# HVAC8-3.net
KiCad netlist of a schematic drawn in EAGLE
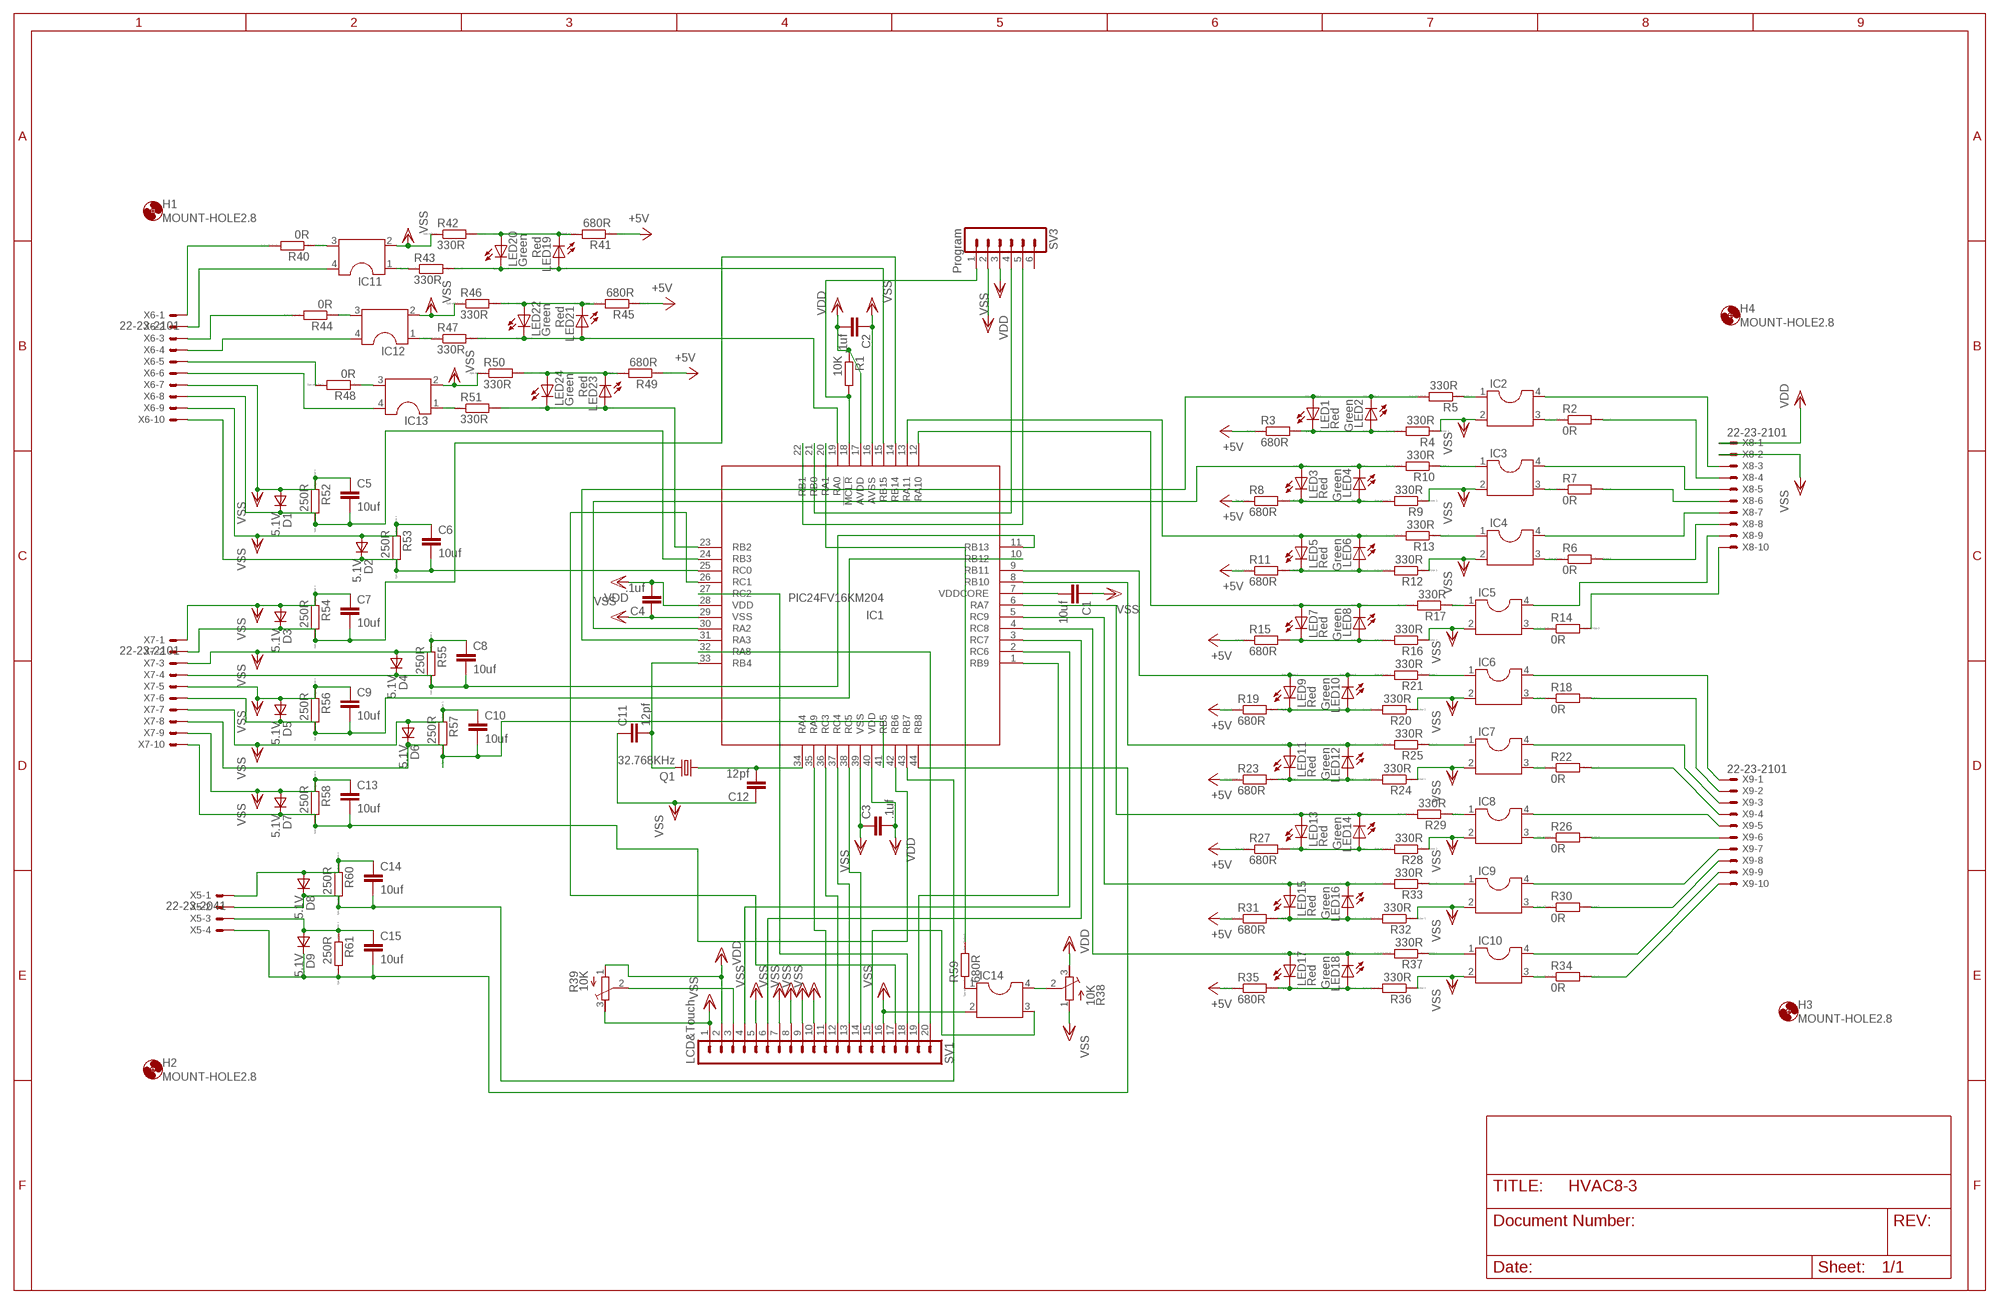
[diagram p0: schematic, sheet 1]

(export (version "E")
  (design (tool "Eeschema 10.0.6"))
  (components
    (comp (ref "C1")
      (value "10uf")
      (footprint "eagle-import:C1206")
      (libsource (lib "eagle-import") (part "C-EUC1206"))
    )
    (comp (ref "C2")
      (value ".1uf")
      (footprint "eagle-import:C1206")
      (libsource (lib "eagle-import") (part "C-EUC1206"))
    )
    (comp (ref "C3")
      (value ".1uf")
      (footprint "eagle-import:C1206")
      (libsource (lib "eagle-import") (part "C-EUC1206"))
    )
    (comp (ref "C4")
      (value ".1uf")
      (footprint "eagle-import:C1206")
      (libsource (lib "eagle-import") (part "C-EUC1206"))
    )
    (comp (ref "C5")
      (value "10uf")
      (footprint "eagle-import:C1206")
      (libsource (lib "eagle-import") (part "C-EUC1206"))
    )
    (comp (ref "C6")
      (value "10uf")
      (footprint "eagle-import:C1206")
      (libsource (lib "eagle-import") (part "C-EUC1206"))
    )
    (comp (ref "C7")
      (value "10uf")
      (footprint "eagle-import:C1206")
      (libsource (lib "eagle-import") (part "C-EUC1206"))
    )
    (comp (ref "C8")
      (value "10uf")
      (footprint "eagle-import:C1206")
      (libsource (lib "eagle-import") (part "C-EUC1206"))
    )
    (comp (ref "C9")
      (value "10uf")
      (footprint "eagle-import:C1206")
      (libsource (lib "eagle-import") (part "C-EUC1206"))
    )
    (comp (ref "C10")
      (value "10uf")
      (footprint "eagle-import:C1206")
      (libsource (lib "eagle-import") (part "C-EUC1206"))
    )
    (comp (ref "C11")
      (value "12pf")
      (footprint "eagle-import:C0603")
      (libsource (lib "eagle-import") (part "C-EUC0603"))
    )
    (comp (ref "C12")
      (value "12pf")
      (footprint "eagle-import:C0603")
      (libsource (lib "eagle-import") (part "C-EUC0603"))
    )
    (comp (ref "C13")
      (value "10uf")
      (footprint "eagle-import:C1206")
      (libsource (lib "eagle-import") (part "C-EUC1206"))
    )
    (comp (ref "C14")
      (value "10uf")
      (footprint "eagle-import:C1206")
      (libsource (lib "eagle-import") (part "C-EUC1206"))
    )
    (comp (ref "C15")
      (value "10uf")
      (footprint "eagle-import:C1206")
      (libsource (lib "eagle-import") (part "C-EUC1206"))
    )
    (comp (ref "D1")
      (value "5.1V")
      (footprint "eagle-import:SOD323")
      (fields (field (name "MPN") "CDSOD323-T05C"))
      (libsource (lib "eagle-import") (part "DSOD323"))
    )
    (comp (ref "D2")
      (value "5.1V")
      (footprint "eagle-import:SOD323")
      (fields (field (name "MPN") "CDSOD323-T05C"))
      (libsource (lib "eagle-import") (part "DSOD323"))
    )
    (comp (ref "D3")
      (value "5.1V")
      (footprint "eagle-import:SOD323")
      (fields (field (name "MPN") "CDSOD323-T05C"))
      (libsource (lib "eagle-import") (part "DSOD323"))
    )
    (comp (ref "D4")
      (value "5.1V")
      (footprint "eagle-import:SOD323")
      (fields (field (name "MPN") "CDSOD323-T05C"))
      (libsource (lib "eagle-import") (part "DSOD323"))
    )
    (comp (ref "D5")
      (value "5.1V")
      (footprint "eagle-import:SOD323")
      (fields (field (name "MPN") "CDSOD323-T05C"))
      (libsource (lib "eagle-import") (part "DSOD323"))
    )
    (comp (ref "D6")
      (value "5.1V")
      (footprint "eagle-import:SOD323")
      (fields (field (name "MPN") "CDSOD323-T05C"))
      (libsource (lib "eagle-import") (part "DSOD323"))
    )
    (comp (ref "D7")
      (value "5.1V")
      (footprint "eagle-import:SOD323")
      (fields (field (name "MPN") "CDSOD323-T05C"))
      (libsource (lib "eagle-import") (part "DSOD323"))
    )
    (comp (ref "D8")
      (value "5.1V")
      (footprint "eagle-import:SOD323")
      (fields (field (name "MPN") "CDSOD323-T05C"))
      (libsource (lib "eagle-import") (part "DSOD323"))
    )
    (comp (ref "D9")
      (value "5.1V")
      (footprint "eagle-import:SOD323")
      (fields (field (name "MPN") "CDSOD323-T05C"))
      (libsource (lib "eagle-import") (part "DSOD323"))
    )
    (comp (ref "H1")
      (value "MOUNT-HOLE2.8")
      (footprint "eagle-import:2,8")
      (libsource (lib "eagle-import") (part "MOUNT-HOLE2.8"))
    )
    (comp (ref "H2")
      (value "MOUNT-HOLE2.8")
      (footprint "eagle-import:2,8")
      (libsource (lib "eagle-import") (part "MOUNT-HOLE2.8"))
    )
    (comp (ref "H3")
      (value "MOUNT-HOLE2.8")
      (footprint "eagle-import:2,8")
      (libsource (lib "eagle-import") (part "MOUNT-HOLE2.8"))
    )
    (comp (ref "H4")
      (value "MOUNT-HOLE2.8")
      (footprint "eagle-import:2,8")
      (libsource (lib "eagle-import") (part "MOUNT-HOLE2.8"))
    )
    (comp (ref "IC1")
      (value "PIC24FV16KM204")
      (footprint "eagle-import:TQFP44")
      (libsource (lib "eagle-import") (part "PIC24FV16KM204"))
    )
    (comp (ref "IC2")
      (value "DIL4S")
      (footprint "eagle-import:SOCKET-04")
      (libsource (lib "eagle-import") (part "DIL4S"))
    )
    (comp (ref "IC3")
      (value "DIL4S")
      (footprint "eagle-import:SOCKET-04")
      (libsource (lib "eagle-import") (part "DIL4S"))
    )
    (comp (ref "IC4")
      (value "DIL4S")
      (footprint "eagle-import:SOCKET-04")
      (libsource (lib "eagle-import") (part "DIL4S"))
    )
    (comp (ref "IC5")
      (value "DIL4S")
      (footprint "eagle-import:SOCKET-04")
      (libsource (lib "eagle-import") (part "DIL4S"))
    )
    (comp (ref "IC6")
      (value "DIL4S")
      (footprint "eagle-import:SOCKET-04")
      (libsource (lib "eagle-import") (part "DIL4S"))
    )
    (comp (ref "IC7")
      (value "DIL4S")
      (footprint "eagle-import:SOCKET-04")
      (libsource (lib "eagle-import") (part "DIL4S"))
    )
    (comp (ref "IC8")
      (value "DIL4S")
      (footprint "eagle-import:SOCKET-04")
      (libsource (lib "eagle-import") (part "DIL4S"))
    )
    (comp (ref "IC9")
      (value "DIL4S")
      (footprint "eagle-import:SOCKET-04")
      (libsource (lib "eagle-import") (part "DIL4S"))
    )
    (comp (ref "IC10")
      (value "DIL4S")
      (footprint "eagle-import:SOCKET-04")
      (libsource (lib "eagle-import") (part "DIL4S"))
    )
    (comp (ref "IC11")
      (value "DIL4S")
      (footprint "eagle-import:SOCKET-04")
      (libsource (lib "eagle-import") (part "DIL4S"))
    )
    (comp (ref "IC12")
      (value "DIL4S")
      (footprint "eagle-import:SOCKET-04")
      (libsource (lib "eagle-import") (part "DIL4S"))
    )
    (comp (ref "IC13")
      (value "DIL4S")
      (footprint "eagle-import:SOCKET-04")
      (libsource (lib "eagle-import") (part "DIL4S"))
    )
    (comp (ref "IC14")
      (value "DIL4S")
      (footprint "eagle-import:SOCKET-04")
      (libsource (lib "eagle-import") (part "DIL4S"))
    )
    (comp (ref "LED1")
      (value "Red")
      (footprint "eagle-import:LED_1206")
      (libsource (lib "eagle-import") (part "LED_E"))
    )
    (comp (ref "LED2")
      (value "Green")
      (footprint "eagle-import:LED_1206")
      (libsource (lib "eagle-import") (part "LED_E"))
    )
    (comp (ref "LED3")
      (value "Red")
      (footprint "eagle-import:LED_1206")
      (libsource (lib "eagle-import") (part "LED_E"))
    )
    (comp (ref "LED4")
      (value "Green")
      (footprint "eagle-import:LED_1206")
      (libsource (lib "eagle-import") (part "LED_E"))
    )
    (comp (ref "LED5")
      (value "Red")
      (footprint "eagle-import:LED_1206")
      (libsource (lib "eagle-import") (part "LED_E"))
    )
    (comp (ref "LED6")
      (value "Green")
      (footprint "eagle-import:LED_1206")
      (libsource (lib "eagle-import") (part "LED_E"))
    )
    (comp (ref "LED7")
      (value "Red")
      (footprint "eagle-import:LED_1206")
      (libsource (lib "eagle-import") (part "LED_E"))
    )
    (comp (ref "LED8")
      (value "Green")
      (footprint "eagle-import:LED_1206")
      (libsource (lib "eagle-import") (part "LED_E"))
    )
    (comp (ref "LED9")
      (value "Red")
      (footprint "eagle-import:LED_1206")
      (libsource (lib "eagle-import") (part "LED_E"))
    )
    (comp (ref "LED10")
      (value "Green")
      (footprint "eagle-import:LED_1206")
      (libsource (lib "eagle-import") (part "LED_E"))
    )
    (comp (ref "LED11")
      (value "Red")
      (footprint "eagle-import:LED_1206")
      (libsource (lib "eagle-import") (part "LED_E"))
    )
    (comp (ref "LED12")
      (value "Green")
      (footprint "eagle-import:LED_1206")
      (libsource (lib "eagle-import") (part "LED_E"))
    )
    (comp (ref "LED13")
      (value "Red")
      (footprint "eagle-import:LED_1206")
      (libsource (lib "eagle-import") (part "LED_E"))
    )
    (comp (ref "LED14")
      (value "Green")
      (footprint "eagle-import:LED_1206")
      (libsource (lib "eagle-import") (part "LED_E"))
    )
    (comp (ref "LED15")
      (value "Red")
      (footprint "eagle-import:LED_1206")
      (libsource (lib "eagle-import") (part "LED_E"))
    )
    (comp (ref "LED16")
      (value "Green")
      (footprint "eagle-import:LED_1206")
      (libsource (lib "eagle-import") (part "LED_E"))
    )
    (comp (ref "LED17")
      (value "Red")
      (footprint "eagle-import:LED_1206")
      (libsource (lib "eagle-import") (part "LED_E"))
    )
    (comp (ref "LED18")
      (value "Green")
      (footprint "eagle-import:LED_1206")
      (libsource (lib "eagle-import") (part "LED_E"))
    )
    (comp (ref "LED19")
      (value "Red")
      (footprint "eagle-import:LED_1206")
      (libsource (lib "eagle-import") (part "LED_E"))
    )
    (comp (ref "LED20")
      (value "Green")
      (footprint "eagle-import:LED_1206")
      (libsource (lib "eagle-import") (part "LED_E"))
    )
    (comp (ref "LED21")
      (value "Red")
      (footprint "eagle-import:LED_1206")
      (libsource (lib "eagle-import") (part "LED_E"))
    )
    (comp (ref "LED22")
      (value "Green")
      (footprint "eagle-import:LED_1206")
      (libsource (lib "eagle-import") (part "LED_E"))
    )
    (comp (ref "LED23")
      (value "Red")
      (footprint "eagle-import:LED_1206")
      (libsource (lib "eagle-import") (part "LED_E"))
    )
    (comp (ref "LED24")
      (value "Green")
      (footprint "eagle-import:LED_1206")
      (libsource (lib "eagle-import") (part "LED_E"))
    )
    (comp (ref "Q1")
      (value "32.768KHz")
      (footprint "eagle-import:TC26H")
      (libsource (lib "eagle-import") (part "CRYSTALTC26H"))
    )
    (comp (ref "R1")
      (value "10K")
      (footprint "eagle-import:R1206")
      (libsource (lib "eagle-import") (part "R-EU_R1206"))
    )
    (comp (ref "R2")
      (value "0R")
      (footprint "eagle-import:R1206")
      (libsource (lib "eagle-import") (part "RR1206"))
    )
    (comp (ref "R3")
      (value "680R")
      (footprint "eagle-import:R1206")
      (libsource (lib "eagle-import") (part "RR1206"))
    )
    (comp (ref "R4")
      (value "330R")
      (footprint "eagle-import:R1206")
      (libsource (lib "eagle-import") (part "RR1206"))
    )
    (comp (ref "R5")
      (value "330R")
      (footprint "eagle-import:R1206")
      (libsource (lib "eagle-import") (part "RR1206"))
    )
    (comp (ref "R6")
      (value "0R")
      (footprint "eagle-import:R1206")
      (libsource (lib "eagle-import") (part "RR1206"))
    )
    (comp (ref "R7")
      (value "0R")
      (footprint "eagle-import:R1206")
      (libsource (lib "eagle-import") (part "RR1206"))
    )
    (comp (ref "R8")
      (value "680R")
      (footprint "eagle-import:R1206")
      (libsource (lib "eagle-import") (part "RR1206"))
    )
    (comp (ref "R9")
      (value "330R")
      (footprint "eagle-import:R1206")
      (libsource (lib "eagle-import") (part "RR1206"))
    )
    (comp (ref "R10")
      (value "330R")
      (footprint "eagle-import:R1206")
      (libsource (lib "eagle-import") (part "RR1206"))
    )
    (comp (ref "R11")
      (value "680R")
      (footprint "eagle-import:R1206")
      (libsource (lib "eagle-import") (part "RR1206"))
    )
    (comp (ref "R12")
      (value "330R")
      (footprint "eagle-import:R1206")
      (libsource (lib "eagle-import") (part "RR1206"))
    )
    (comp (ref "R13")
      (value "330R")
      (footprint "eagle-import:R1206")
      (libsource (lib "eagle-import") (part "RR1206"))
    )
    (comp (ref "R14")
      (value "0R")
      (footprint "eagle-import:R1206")
      (libsource (lib "eagle-import") (part "RR1206"))
    )
    (comp (ref "R15")
      (value "680R")
      (footprint "eagle-import:R1206")
      (libsource (lib "eagle-import") (part "RR1206"))
    )
    (comp (ref "R16")
      (value "330R")
      (footprint "eagle-import:R1206")
      (libsource (lib "eagle-import") (part "RR1206"))
    )
    (comp (ref "R17")
      (value "330R")
      (footprint "eagle-import:R1206")
      (libsource (lib "eagle-import") (part "RR1206"))
    )
    (comp (ref "R18")
      (value "0R")
      (footprint "eagle-import:R1206")
      (libsource (lib "eagle-import") (part "RR1206"))
    )
    (comp (ref "R19")
      (value "680R")
      (footprint "eagle-import:R1206")
      (libsource (lib "eagle-import") (part "RR1206"))
    )
    (comp (ref "R20")
      (value "330R")
      (footprint "eagle-import:R1206")
      (libsource (lib "eagle-import") (part "RR1206"))
    )
    (comp (ref "R21")
      (value "330R")
      (footprint "eagle-import:R1206")
      (libsource (lib "eagle-import") (part "RR1206"))
    )
    (comp (ref "R22")
      (value "0R")
      (footprint "eagle-import:R1206")
      (libsource (lib "eagle-import") (part "RR1206"))
    )
    (comp (ref "R23")
      (value "680R")
      (footprint "eagle-import:R1206")
      (libsource (lib "eagle-import") (part "RR1206"))
    )
    (comp (ref "R24")
      (value "330R")
      (footprint "eagle-import:R1206")
      (libsource (lib "eagle-import") (part "RR1206"))
    )
    (comp (ref "R25")
      (value "330R")
      (footprint "eagle-import:R1206")
      (libsource (lib "eagle-import") (part "RR1206"))
    )
    (comp (ref "R26")
      (value "0R")
      (footprint "eagle-import:R1206")
      (libsource (lib "eagle-import") (part "RR1206"))
    )
    (comp (ref "R27")
      (value "680R")
      (footprint "eagle-import:R1206")
      (libsource (lib "eagle-import") (part "RR1206"))
    )
    (comp (ref "R28")
      (value "330R")
      (footprint "eagle-import:R1206")
      (libsource (lib "eagle-import") (part "RR1206"))
    )
    (comp (ref "R29")
      (value "330R")
      (footprint "eagle-import:R1206")
      (libsource (lib "eagle-import") (part "RR1206"))
    )
    (comp (ref "R30")
      (value "0R")
      (footprint "eagle-import:R1206")
      (libsource (lib "eagle-import") (part "RR1206"))
    )
    (comp (ref "R31")
      (value "680R")
      (footprint "eagle-import:R1206")
      (libsource (lib "eagle-import") (part "RR1206"))
    )
    (comp (ref "R32")
      (value "330R")
      (footprint "eagle-import:R1206")
      (libsource (lib "eagle-import") (part "RR1206"))
    )
    (comp (ref "R33")
      (value "330R")
      (footprint "eagle-import:R1206")
      (libsource (lib "eagle-import") (part "RR1206"))
    )
    (comp (ref "R34")
      (value "0R")
      (footprint "eagle-import:R1206")
      (libsource (lib "eagle-import") (part "RR1206"))
    )
    (comp (ref "R35")
      (value "680R")
      (footprint "eagle-import:R1206")
      (libsource (lib "eagle-import") (part "RR1206"))
    )
    (comp (ref "R36")
      (value "330R")
      (footprint "eagle-import:R1206")
      (libsource (lib "eagle-import") (part "RR1206"))
    )
    (comp (ref "R37")
      (value "330R")
      (footprint "eagle-import:R1206")
      (libsource (lib "eagle-import") (part "RR1206"))
    )
    (comp (ref "R38")
      (value "10K")
      (footprint "eagle-import:RTRIM3296W")
      (libsource (lib "eagle-import") (part "R-TRIMM3296W"))
    )
    (comp (ref "R39")
      (value "10K")
      (footprint "eagle-import:RTRIM3296W")
      (libsource (lib "eagle-import") (part "R-TRIMM3296W"))
    )
    (comp (ref "R40")
      (value "0R")
      (footprint "eagle-import:R1206")
      (libsource (lib "eagle-import") (part "RR1206"))
    )
    (comp (ref "R41")
      (value "680R")
      (footprint "eagle-import:R1206")
      (libsource (lib "eagle-import") (part "RR1206"))
    )
    (comp (ref "R42")
      (value "330R")
      (footprint "eagle-import:R1206")
      (libsource (lib "eagle-import") (part "RR1206"))
    )
    (comp (ref "R43")
      (value "330R")
      (footprint "eagle-import:R1206")
      (libsource (lib "eagle-import") (part "RR1206"))
    )
    (comp (ref "R44")
      (value "0R")
      (footprint "eagle-import:R1206")
      (libsource (lib "eagle-import") (part "RR1206"))
    )
    (comp (ref "R45")
      (value "680R")
      (footprint "eagle-import:R1206")
      (libsource (lib "eagle-import") (part "RR1206"))
    )
    (comp (ref "R46")
      (value "330R")
      (footprint "eagle-import:R1206")
      (libsource (lib "eagle-import") (part "RR1206"))
    )
    (comp (ref "R47")
      (value "330R")
      (footprint "eagle-import:R1206")
      (libsource (lib "eagle-import") (part "RR1206"))
    )
    (comp (ref "R48")
      (value "0R")
      (footprint "eagle-import:R1206")
      (libsource (lib "eagle-import") (part "RR1206"))
    )
    (comp (ref "R49")
      (value "680R")
      (footprint "eagle-import:R1206")
      (libsource (lib "eagle-import") (part "RR1206"))
    )
    (comp (ref "R50")
      (value "330R")
      (footprint "eagle-import:R1206")
      (libsource (lib "eagle-import") (part "RR1206"))
    )
    (comp (ref "R51")
      (value "330R")
      (footprint "eagle-import:R1206")
      (libsource (lib "eagle-import") (part "RR1206"))
    )
    (comp (ref "R52")
      (value "250R")
      (footprint "eagle-import:R1206")
      (libsource (lib "eagle-import") (part "RR1206"))
    )
    (comp (ref "R53")
      (value "250R")
      (footprint "eagle-import:R1206")
      (libsource (lib "eagle-import") (part "RR1206"))
    )
    (comp (ref "R54")
      (value "250R")
      (footprint "eagle-import:R1206")
      (libsource (lib "eagle-import") (part "RR1206"))
    )
    (comp (ref "R55")
      (value "250R")
      (footprint "eagle-import:R1206")
      (libsource (lib "eagle-import") (part "RR1206"))
    )
    (comp (ref "R56")
      (value "250R")
      (footprint "eagle-import:R1206")
      (libsource (lib "eagle-import") (part "RR1206"))
    )
    (comp (ref "R57")
      (value "250R")
      (footprint "eagle-import:R1206")
      (libsource (lib "eagle-import") (part "RR1206"))
    )
    (comp (ref "R58")
      (value "250R")
      (footprint "eagle-import:R1206")
      (libsource (lib "eagle-import") (part "RR1206"))
    )
    (comp (ref "R59")
      (value "680R")
      (footprint "eagle-import:R1206")
      (libsource (lib "eagle-import") (part "RR1206"))
    )
    (comp (ref "R60")
      (value "250R")
      (footprint "eagle-import:R1206")
      (libsource (lib "eagle-import") (part "RR1206"))
    )
    (comp (ref "R61")
      (value "250R")
      (footprint "eagle-import:R1206")
      (libsource (lib "eagle-import") (part "RR1206"))
    )
    (comp (ref "SV1")
      (value "LCD&Touch")
      (footprint "eagle-import:MA20-1")
      (libsource (lib "eagle-import") (part "MA20-1"))
    )
    (comp (ref "SV3")
      (value "Program")
      (footprint "eagle-import:MA06-1")
      (libsource (lib "eagle-import") (part "MA06-1"))
    )
    (comp (ref "X5")
      (value "22-23-2041")
      (footprint "eagle-import:22-23-2041")
      (fields (field (name "MF") "MOLEX"))
      (libsource (lib "eagle-import") (part "22-23-2041"))
    )
    (comp (ref "X6")
      (value "22-23-2101")
      (footprint "eagle-import:22-23-2101")
      (fields (field (name "MF") "MOLEX"))
      (libsource (lib "eagle-import") (part "22-23-2101"))
    )
    (comp (ref "X7")
      (value "22-23-2101")
      (footprint "eagle-import:22-23-2101")
      (fields (field (name "MF") "MOLEX"))
      (libsource (lib "eagle-import") (part "22-23-2101"))
    )
    (comp (ref "X8")
      (value "22-23-2101")
      (footprint "eagle-import:22-23-2101")
      (fields (field (name "MF") "MOLEX"))
      (libsource (lib "eagle-import") (part "22-23-2101"))
    )
    (comp (ref "X9")
      (value "22-23-2101")
      (footprint "eagle-import:22-23-2101")
      (fields (field (name "MF") "MOLEX"))
      (libsource (lib "eagle-import") (part "22-23-2101"))
    )
  )
  (nets
    (net (code "1") (name "+5V") (class "Default")
      (node (ref "R11") (pin "1") (pinfunction "1_1") (pintype "passive"))
      (node (ref "R15") (pin "1") (pinfunction "1_1") (pintype "passive"))
      (node (ref "R19") (pin "1") (pinfunction "1_1") (pintype "passive"))
      (node (ref "R23") (pin "1") (pinfunction "1_1") (pintype "passive"))
      (node (ref "R27") (pin "1") (pinfunction "1_1") (pintype "passive"))
      (node (ref "R3") (pin "1") (pinfunction "1_1") (pintype "passive"))
      (node (ref "R31") (pin "1") (pinfunction "1_1") (pintype "passive"))
      (node (ref "R35") (pin "1") (pinfunction "1_1") (pintype "passive"))
      (node (ref "R41") (pin "1") (pinfunction "1_1") (pintype "passive"))
      (node (ref "R45") (pin "1") (pinfunction "1_1") (pintype "passive"))
      (node (ref "R49") (pin "1") (pinfunction "1_1") (pintype "passive"))
      (node (ref "R8") (pin "1") (pinfunction "1_1") (pintype "passive"))
    )
    (net (code "2") (name "Net-(D1-C)") (class "Default")
      (node (ref "C5") (pin "2") (pinfunction "2_2") (pintype "passive"))
      (node (ref "D1") (pin "1") (pinfunction "C_1") (pintype "passive"))
      (node (ref "IC1") (pin "24") (pinfunction "RB3_24") (pintype "bidirectional"))
      (node (ref "R52") (pin "2") (pinfunction "2_2") (pintype "passive"))
      (node (ref "X6") (pin "8") (pinfunction "S_8") (pintype "passive"))
    )
    (net (code "3") (name "Net-(D2-C)") (class "Default")
      (node (ref "C6") (pin "2") (pinfunction "2_2") (pintype "passive"))
      (node (ref "D2") (pin "1") (pinfunction "C_1") (pintype "passive"))
      (node (ref "IC1") (pin "25") (pinfunction "RC0_25") (pintype "bidirectional"))
      (node (ref "R53") (pin "2") (pinfunction "2_2") (pintype "passive"))
      (node (ref "X6") (pin "10") (pinfunction "S_10") (pintype "passive"))
    )
    (net (code "4") (name "Net-(D3-C)") (class "Default")
      (node (ref "C7") (pin "2") (pinfunction "2_2") (pintype "passive"))
      (node (ref "D3") (pin "1") (pinfunction "C_1") (pintype "passive"))
      (node (ref "IC1") (pin "14") (pinfunction "RB14_14") (pintype "bidirectional"))
      (node (ref "R54") (pin "2") (pinfunction "2_2") (pintype "passive"))
      (node (ref "X7") (pin "2") (pinfunction "S_2") (pintype "passive"))
    )
    (net (code "5") (name "Net-(D4-C)") (class "Default")
      (node (ref "C8") (pin "2") (pinfunction "2_2") (pintype "passive"))
      (node (ref "D4") (pin "1") (pinfunction "C_1") (pintype "passive"))
      (node (ref "IC1") (pin "11") (pinfunction "RB13_11") (pintype "bidirectional"))
      (node (ref "R55") (pin "2") (pinfunction "2_2") (pintype "passive"))
      (node (ref "X7") (pin "4") (pinfunction "S_4") (pintype "passive"))
    )
    (net (code "6") (name "Net-(D5-C)") (class "Default")
      (node (ref "C9") (pin "2") (pinfunction "2_2") (pintype "passive"))
      (node (ref "D5") (pin "1") (pinfunction "C_1") (pintype "passive"))
      (node (ref "IC1") (pin "10") (pinfunction "RB12_10") (pintype "bidirectional"))
      (node (ref "R56") (pin "2") (pinfunction "2_2") (pintype "passive"))
      (node (ref "X7") (pin "6") (pinfunction "S_6") (pintype "passive"))
    )
    (net (code "7") (name "Net-(D6-C)") (class "Default")
      (node (ref "C10") (pin "2") (pinfunction "2_2") (pintype "passive"))
      (node (ref "D6") (pin "1") (pinfunction "C_1") (pintype "passive"))
      (node (ref "IC1") (pin "41") (pinfunction "RB5_41") (pintype "bidirectional"))
      (node (ref "R57") (pin "2") (pinfunction "2_2") (pintype "passive"))
      (node (ref "X7") (pin "8") (pinfunction "S_8") (pintype "passive"))
    )
    (net (code "8") (name "Net-(D7-C)") (class "Default")
      (node (ref "C13") (pin "2") (pinfunction "2_2") (pintype "passive"))
      (node (ref "D7") (pin "1") (pinfunction "C_1") (pintype "passive"))
      (node (ref "IC1") (pin "42") (pinfunction "RB6_42") (pintype "bidirectional"))
      (node (ref "R58") (pin "2") (pinfunction "2_2") (pintype "passive"))
      (node (ref "X7") (pin "10") (pinfunction "S_10") (pintype "passive"))
    )
    (net (code "9") (name "Net-(D8-A)") (class "Default")
      (node (ref "C14") (pin "1") (pinfunction "1_1") (pintype "passive"))
      (node (ref "D8") (pin "2") (pinfunction "A_2") (pintype "passive"))
      (node (ref "R60") (pin "1") (pinfunction "1_1") (pintype "passive"))
      (node (ref "X5") (pin "1") (pinfunction "S_1") (pintype "passive"))
    )
    (net (code "10") (name "Net-(D8-C)") (class "Default")
      (node (ref "C14") (pin "2") (pinfunction "2_2") (pintype "passive"))
      (node (ref "D8") (pin "1") (pinfunction "C_1") (pintype "passive"))
      (node (ref "IC1") (pin "43") (pinfunction "RB7_43") (pintype "bidirectional"))
      (node (ref "R60") (pin "2") (pinfunction "2_2") (pintype "passive"))
      (node (ref "X5") (pin "2") (pinfunction "S_2") (pintype "passive"))
    )
    (net (code "11") (name "Net-(D9-A)") (class "Default")
      (node (ref "C15") (pin "1") (pinfunction "1_1") (pintype "passive"))
      (node (ref "D9") (pin "2") (pinfunction "A_2") (pintype "passive"))
      (node (ref "R61") (pin "1") (pinfunction "1_1") (pintype "passive"))
      (node (ref "X5") (pin "3") (pinfunction "S_3") (pintype "passive"))
    )
    (net (code "12") (name "Net-(D9-C)") (class "Default")
      (node (ref "C15") (pin "2") (pinfunction "2_2") (pintype "passive"))
      (node (ref "D9") (pin "1") (pinfunction "C_1") (pintype "passive"))
      (node (ref "IC1") (pin "44") (pinfunction "RB8_44") (pintype "bidirectional"))
      (node (ref "R61") (pin "2") (pinfunction "2_2") (pintype "passive"))
      (node (ref "X5") (pin "4") (pinfunction "S_4") (pintype "passive"))
    )
    (net (code "13") (name "Net-(IC1-RA0)") (class "Default")
      (node (ref "IC1") (pin "19") (pinfunction "RA0_19") (pintype "bidirectional"))
      (node (ref "LED21") (pin "A") (pinfunction "A_A") (pintype "passive"))
      (node (ref "LED22") (pin "C") (pinfunction "C_C") (pintype "passive"))
      (node (ref "R47") (pin "2") (pinfunction "2_2") (pintype "passive"))
    )
    (net (code "14") (name "Net-(IC1-RA1)") (class "Default")
      (node (ref "IC1") (pin "20") (pinfunction "RA1_20") (pintype "bidirectional"))
      (node (ref "R59") (pin "2") (pinfunction "2_2") (pintype "passive"))
    )
    (net (code "15") (name "Net-(IC1-RA2)") (class "Default")
      (node (ref "IC1") (pin "30") (pinfunction "RA2_30") (pintype "bidirectional"))
      (node (ref "LED3") (pin "A") (pinfunction "A_A") (pintype "passive"))
      (node (ref "LED4") (pin "C") (pinfunction "C_C") (pintype "passive"))
      (node (ref "R10") (pin "2") (pinfunction "2_2") (pintype "passive"))
    )
    (net (code "16") (name "Net-(IC1-RA3)") (class "Default")
      (node (ref "IC1") (pin "31") (pinfunction "RA3_31") (pintype "bidirectional"))
      (node (ref "LED1") (pin "A") (pinfunction "A_A") (pintype "passive"))
      (node (ref "LED2") (pin "C") (pinfunction "C_C") (pintype "passive"))
      (node (ref "R5") (pin "2") (pinfunction "2_2") (pintype "passive"))
    )
    (net (code "17") (name "Net-(IC1-RA4)") (class "Default")
      (node (ref "C12") (pin "2") (pinfunction "2_2") (pintype "passive"))
      (node (ref "IC1") (pin "34") (pinfunction "RA4_34") (pintype "bidirectional"))
      (node (ref "Q1") (pin "1") (pinfunction "1_1") (pintype "passive"))
    )
    (net (code "18") (name "Net-(IC1-RA7)") (class "Default")
      (node (ref "IC1") (pin "6") (pinfunction "RA7_6") (pintype "bidirectional"))
      (node (ref "LED13") (pin "A") (pinfunction "A_A") (pintype "passive"))
      (node (ref "LED14") (pin "C") (pinfunction "C_C") (pintype "passive"))
      (node (ref "R29") (pin "2") (pinfunction "2_2") (pintype "passive"))
    )
    (net (code "19") (name "Net-(IC1-RA8)") (class "Default")
      (node (ref "IC1") (pin "32") (pinfunction "RA8_32") (pintype "bidirectional"))
      (node (ref "SV1") (pin "20") (pinfunction "20_20") (pintype "passive"))
    )
    (net (code "20") (name "Net-(IC1-RA9)") (class "Default")
      (node (ref "IC1") (pin "35") (pinfunction "RA9_35") (pintype "bidirectional"))
      (node (ref "SV1") (pin "11") (pinfunction "11_11") (pintype "passive"))
    )
    (net (code "21") (name "Net-(IC1-RA10)") (class "Default")
      (node (ref "IC1") (pin "12") (pinfunction "RA10_12") (pintype "bidirectional"))
      (node (ref "LED7") (pin "A") (pinfunction "A_A") (pintype "passive"))
      (node (ref "LED8") (pin "C") (pinfunction "C_C") (pintype "passive"))
      (node (ref "R17") (pin "2") (pinfunction "2_2") (pintype "passive"))
    )
    (net (code "22") (name "Net-(IC1-RA11)") (class "Default")
      (node (ref "IC1") (pin "13") (pinfunction "RA11_13") (pintype "bidirectional"))
      (node (ref "LED5") (pin "A") (pinfunction "A_A") (pintype "passive"))
      (node (ref "LED6") (pin "C") (pinfunction "C_C") (pintype "passive"))
      (node (ref "R13") (pin "2") (pinfunction "2_2") (pintype "passive"))
    )
    (net (code "23") (name "Net-(IC1-RB0)") (class "Default")
      (node (ref "IC1") (pin "21") (pinfunction "RB0_21") (pintype "bidirectional"))
      (node (ref "SV3") (pin "4") (pinfunction "4_4") (pintype "passive"))
    )
    (net (code "24") (name "Net-(IC1-RB1)") (class "Default")
      (node (ref "IC1") (pin "22") (pinfunction "RB1_22") (pintype "bidirectional"))
      (node (ref "SV3") (pin "5") (pinfunction "5_5") (pintype "passive"))
    )
    (net (code "25") (name "Net-(IC1-RB2)") (class "Default")
      (node (ref "IC1") (pin "23") (pinfunction "RB2_23") (pintype "bidirectional"))
      (node (ref "LED23") (pin "A") (pinfunction "A_A") (pintype "passive"))
      (node (ref "LED24") (pin "C") (pinfunction "C_C") (pintype "passive"))
      (node (ref "R51") (pin "2") (pinfunction "2_2") (pintype "passive"))
    )
    (net (code "26") (name "Net-(IC1-RB4)") (class "Default")
      (node (ref "C11") (pin "2") (pinfunction "2_2") (pintype "passive"))
      (node (ref "IC1") (pin "33") (pinfunction "RB4_33") (pintype "bidirectional"))
      (node (ref "Q1") (pin "2") (pinfunction "2_2") (pintype "passive"))
    )
    (net (code "27") (name "Net-(IC1-RB9)") (class "Default")
      (node (ref "IC1") (pin "1") (pinfunction "RB9_1") (pintype "bidirectional"))
      (node (ref "SV1") (pin "19") (pinfunction "19_19") (pintype "passive"))
    )
    (net (code "28") (name "Net-(IC1-RB10)") (class "Default")
      (node (ref "IC1") (pin "8") (pinfunction "RB10_8") (pintype "bidirectional"))
      (node (ref "LED11") (pin "A") (pinfunction "A_A") (pintype "passive"))
      (node (ref "LED12") (pin "C") (pinfunction "C_C") (pintype "passive"))
      (node (ref "R25") (pin "2") (pinfunction "2_2") (pintype "passive"))
    )
    (net (code "29") (name "Net-(IC1-RB11)") (class "Default")
      (node (ref "IC1") (pin "9") (pinfunction "RB11_9") (pintype "bidirectional"))
      (node (ref "LED10") (pin "C") (pinfunction "C_C") (pintype "passive"))
      (node (ref "LED9") (pin "A") (pinfunction "A_A") (pintype "passive"))
      (node (ref "R21") (pin "2") (pinfunction "2_2") (pintype "passive"))
    )
    (net (code "30") (name "Net-(IC1-RB15)") (class "Default")
      (node (ref "IC1") (pin "15") (pinfunction "RB15_15") (pintype "bidirectional"))
      (node (ref "LED19") (pin "A") (pinfunction "A_A") (pintype "passive"))
      (node (ref "LED20") (pin "C") (pinfunction "C_C") (pintype "passive"))
      (node (ref "R43") (pin "2") (pinfunction "2_2") (pintype "passive"))
    )
    (net (code "31") (name "Net-(IC1-RC1)") (class "Default")
      (node (ref "IC1") (pin "26") (pinfunction "RC1_26") (pintype "bidirectional"))
      (node (ref "SV1") (pin "17") (pinfunction "17_17") (pintype "passive"))
    )
    (net (code "32") (name "Net-(IC1-RC2)") (class "Default")
      (node (ref "IC1") (pin "27") (pinfunction "RC2_27") (pintype "bidirectional"))
      (node (ref "SV1") (pin "18") (pinfunction "18_18") (pintype "passive"))
    )
    (net (code "33") (name "Net-(IC1-RC3)") (class "Default")
      (node (ref "IC1") (pin "36") (pinfunction "RC3_36") (pintype "bidirectional"))
      (node (ref "SV1") (pin "12") (pinfunction "12_12") (pintype "passive"))
    )
    (net (code "34") (name "Net-(IC1-RC4)") (class "Default")
      (node (ref "IC1") (pin "37") (pinfunction "RC4_37") (pintype "bidirectional"))
      (node (ref "SV1") (pin "13") (pinfunction "13_13") (pintype "passive"))
    )
    (net (code "35") (name "Net-(IC1-RC5)") (class "Default")
      (node (ref "IC1") (pin "38") (pinfunction "RC5_38") (pintype "bidirectional"))
      (node (ref "SV1") (pin "14") (pinfunction "14_14") (pintype "passive"))
    )
    (net (code "36") (name "Net-(IC1-RC6)") (class "Default")
      (node (ref "IC1") (pin "2") (pinfunction "RC6_2") (pintype "bidirectional"))
      (node (ref "SV1") (pin "4") (pinfunction "4_4") (pintype "passive"))
    )
    (net (code "37") (name "Net-(IC1-RC7)") (class "Default")
      (node (ref "IC1") (pin "3") (pinfunction "RC7_3") (pintype "bidirectional"))
      (node (ref "SV1") (pin "6") (pinfunction "6_6") (pintype "passive"))
    )
    (net (code "38") (name "Net-(IC1-RC8)") (class "Default")
      (node (ref "IC1") (pin "4") (pinfunction "RC8_4") (pintype "bidirectional"))
      (node (ref "LED17") (pin "A") (pinfunction "A_A") (pintype "passive"))
      (node (ref "LED18") (pin "C") (pinfunction "C_C") (pintype "passive"))
      (node (ref "R37") (pin "2") (pinfunction "2_2") (pintype "passive"))
    )
    (net (code "39") (name "Net-(IC1-RC9)") (class "Default")
      (node (ref "IC1") (pin "5") (pinfunction "RC9_5") (pintype "bidirectional"))
      (node (ref "LED15") (pin "A") (pinfunction "A_A") (pintype "passive"))
      (node (ref "LED16") (pin "C") (pinfunction "C_C") (pintype "passive"))
      (node (ref "R33") (pin "2") (pinfunction "2_2") (pintype "passive"))
    )
    (net (code "40") (name "Net-(IC1-VDDCORE)") (class "Default")
      (node (ref "C1") (pin "2") (pinfunction "2_2") (pintype "passive"))
      (node (ref "IC1") (pin "7") (pinfunction "VDDCORE_7") (pintype "power_in"))
    )
    (net (code "41") (name "Net-(IC1-~{MCLR})") (class "Default")
      (node (ref "IC1") (pin "18") (pinfunction "~{MCLR}_18") (pintype "bidirectional"))
      (node (ref "R1") (pin "2") (pinfunction "2_2") (pintype "passive"))
      (node (ref "SV3") (pin "1") (pinfunction "1_1") (pintype "passive"))
    )
    (net (code "42") (name "Net-(IC2-Pad1)") (class "Default")
      (node (ref "IC2") (pin "1") (pinfunction "1_1") (pintype "passive"))
      (node (ref "R5") (pin "1") (pinfunction "1_1") (pintype "passive"))
    )
    (net (code "43") (name "Net-(IC2-Pad3)") (class "Default")
      (node (ref "IC2") (pin "3") (pinfunction "3_3") (pintype "passive"))
      (node (ref "R2") (pin "1") (pinfunction "1_1") (pintype "passive"))
    )
    (net (code "44") (name "Net-(IC3-Pad1)") (class "Default")
      (node (ref "IC3") (pin "1") (pinfunction "1_1") (pintype "passive"))
      (node (ref "R10") (pin "1") (pinfunction "1_1") (pintype "passive"))
    )
    (net (code "45") (name "Net-(IC3-Pad3)") (class "Default")
      (node (ref "IC3") (pin "3") (pinfunction "3_3") (pintype "passive"))
      (node (ref "R7") (pin "1") (pinfunction "1_1") (pintype "passive"))
    )
    (net (code "46") (name "Net-(IC4-Pad1)") (class "Default")
      (node (ref "IC4") (pin "1") (pinfunction "1_1") (pintype "passive"))
      (node (ref "R13") (pin "1") (pinfunction "1_1") (pintype "passive"))
    )
    (net (code "47") (name "Net-(IC4-Pad3)") (class "Default")
      (node (ref "IC4") (pin "3") (pinfunction "3_3") (pintype "passive"))
      (node (ref "R6") (pin "1") (pinfunction "1_1") (pintype "passive"))
    )
    (net (code "48") (name "Net-(IC5-Pad1)") (class "Default")
      (node (ref "IC5") (pin "1") (pinfunction "1_1") (pintype "passive"))
      (node (ref "R17") (pin "1") (pinfunction "1_1") (pintype "passive"))
    )
    (net (code "49") (name "Net-(IC5-Pad3)") (class "Default")
      (node (ref "IC5") (pin "3") (pinfunction "3_3") (pintype "passive"))
      (node (ref "R14") (pin "1") (pinfunction "1_1") (pintype "passive"))
    )
    (net (code "50") (name "Net-(IC6-Pad1)") (class "Default")
      (node (ref "IC6") (pin "1") (pinfunction "1_1") (pintype "passive"))
      (node (ref "R21") (pin "1") (pinfunction "1_1") (pintype "passive"))
    )
    (net (code "51") (name "Net-(IC6-Pad3)") (class "Default")
      (node (ref "IC6") (pin "3") (pinfunction "3_3") (pintype "passive"))
      (node (ref "R18") (pin "1") (pinfunction "1_1") (pintype "passive"))
    )
    (net (code "52") (name "Net-(IC7-Pad1)") (class "Default")
      (node (ref "IC7") (pin "1") (pinfunction "1_1") (pintype "passive"))
      (node (ref "R25") (pin "1") (pinfunction "1_1") (pintype "passive"))
    )
    (net (code "53") (name "Net-(IC7-Pad3)") (class "Default")
      (node (ref "IC7") (pin "3") (pinfunction "3_3") (pintype "passive"))
      (node (ref "R22") (pin "1") (pinfunction "1_1") (pintype "passive"))
    )
    (net (code "54") (name "Net-(IC8-Pad1)") (class "Default")
      (node (ref "IC8") (pin "1") (pinfunction "1_1") (pintype "passive"))
      (node (ref "R29") (pin "1") (pinfunction "1_1") (pintype "passive"))
    )
    (net (code "55") (name "Net-(IC8-Pad3)") (class "Default")
      (node (ref "IC8") (pin "3") (pinfunction "3_3") (pintype "passive"))
      (node (ref "R26") (pin "1") (pinfunction "1_1") (pintype "passive"))
    )
    (net (code "56") (name "Net-(IC9-Pad1)") (class "Default")
      (node (ref "IC9") (pin "1") (pinfunction "1_1") (pintype "passive"))
      (node (ref "R33") (pin "1") (pinfunction "1_1") (pintype "passive"))
    )
    (net (code "57") (name "Net-(IC9-Pad3)") (class "Default")
      (node (ref "IC9") (pin "3") (pinfunction "3_3") (pintype "passive"))
      (node (ref "R30") (pin "1") (pinfunction "1_1") (pintype "passive"))
    )
    (net (code "58") (name "Net-(IC10-Pad1)") (class "Default")
      (node (ref "IC10") (pin "1") (pinfunction "1_1") (pintype "passive"))
      (node (ref "R37") (pin "1") (pinfunction "1_1") (pintype "passive"))
    )
    (net (code "59") (name "Net-(IC10-Pad3)") (class "Default")
      (node (ref "IC10") (pin "3") (pinfunction "3_3") (pintype "passive"))
      (node (ref "R34") (pin "1") (pinfunction "1_1") (pintype "passive"))
    )
    (net (code "60") (name "Net-(IC11-Pad1)") (class "Default")
      (node (ref "IC11") (pin "1") (pinfunction "1_1") (pintype "passive"))
      (node (ref "R43") (pin "1") (pinfunction "1_1") (pintype "passive"))
    )
    (net (code "61") (name "Net-(IC11-Pad3)") (class "Default")
      (node (ref "IC11") (pin "3") (pinfunction "3_3") (pintype "passive"))
      (node (ref "R40") (pin "1") (pinfunction "1_1") (pintype "passive"))
    )
    (net (code "62") (name "Net-(IC12-Pad1)") (class "Default")
      (node (ref "IC12") (pin "1") (pinfunction "1_1") (pintype "passive"))
      (node (ref "R47") (pin "1") (pinfunction "1_1") (pintype "passive"))
    )
    (net (code "63") (name "Net-(IC12-Pad3)") (class "Default")
      (node (ref "IC12") (pin "3") (pinfunction "3_3") (pintype "passive"))
      (node (ref "R44") (pin "1") (pinfunction "1_1") (pintype "passive"))
    )
    (net (code "64") (name "Net-(IC13-Pad1)") (class "Default")
      (node (ref "IC13") (pin "1") (pinfunction "1_1") (pintype "passive"))
      (node (ref "R51") (pin "1") (pinfunction "1_1") (pintype "passive"))
    )
    (net (code "65") (name "Net-(IC13-Pad3)") (class "Default")
      (node (ref "IC13") (pin "3") (pinfunction "3_3") (pintype "passive"))
      (node (ref "R48") (pin "1") (pinfunction "1_1") (pintype "passive"))
    )
    (net (code "66") (name "Net-(IC14-Pad1)") (class "Default")
      (node (ref "IC14") (pin "1") (pinfunction "1_1") (pintype "passive"))
      (node (ref "R59") (pin "1") (pinfunction "1_1") (pintype "passive"))
    )
    (net (code "67") (name "Net-(IC14-Pad3)") (class "Default")
      (node (ref "IC14") (pin "3") (pinfunction "3_3") (pintype "passive"))
      (node (ref "SV1") (pin "15") (pinfunction "15_15") (pintype "passive"))
    )
    (net (code "68") (name "Net-(LED1-PadC)") (class "Default")
      (node (ref "LED1") (pin "C") (pinfunction "C_C") (pintype "passive"))
      (node (ref "LED2") (pin "A") (pinfunction "A_A") (pintype "passive"))
      (node (ref "R3") (pin "2") (pinfunction "2_2") (pintype "passive"))
      (node (ref "R4") (pin "2") (pinfunction "2_2") (pintype "passive"))
    )
    (net (code "69") (name "Net-(LED3-PadC)") (class "Default")
      (node (ref "LED3") (pin "C") (pinfunction "C_C") (pintype "passive"))
      (node (ref "LED4") (pin "A") (pinfunction "A_A") (pintype "passive"))
      (node (ref "R8") (pin "2") (pinfunction "2_2") (pintype "passive"))
      (node (ref "R9") (pin "2") (pinfunction "2_2") (pintype "passive"))
    )
    (net (code "70") (name "Net-(LED5-PadC)") (class "Default")
      (node (ref "LED5") (pin "C") (pinfunction "C_C") (pintype "passive"))
      (node (ref "LED6") (pin "A") (pinfunction "A_A") (pintype "passive"))
      (node (ref "R11") (pin "2") (pinfunction "2_2") (pintype "passive"))
      (node (ref "R12") (pin "2") (pinfunction "2_2") (pintype "passive"))
    )
    (net (code "71") (name "Net-(LED7-PadC)") (class "Default")
      (node (ref "LED7") (pin "C") (pinfunction "C_C") (pintype "passive"))
      (node (ref "LED8") (pin "A") (pinfunction "A_A") (pintype "passive"))
      (node (ref "R15") (pin "2") (pinfunction "2_2") (pintype "passive"))
      (node (ref "R16") (pin "2") (pinfunction "2_2") (pintype "passive"))
    )
    (net (code "72") (name "Net-(LED10-PadA)") (class "Default")
      (node (ref "LED10") (pin "A") (pinfunction "A_A") (pintype "passive"))
      (node (ref "LED9") (pin "C") (pinfunction "C_C") (pintype "passive"))
      (node (ref "R19") (pin "2") (pinfunction "2_2") (pintype "passive"))
      (node (ref "R20") (pin "2") (pinfunction "2_2") (pintype "passive"))
    )
    (net (code "73") (name "Net-(LED11-PadC)") (class "Default")
      (node (ref "LED11") (pin "C") (pinfunction "C_C") (pintype "passive"))
      (node (ref "LED12") (pin "A") (pinfunction "A_A") (pintype "passive"))
      (node (ref "R23") (pin "2") (pinfunction "2_2") (pintype "passive"))
      (node (ref "R24") (pin "2") (pinfunction "2_2") (pintype "passive"))
    )
    (net (code "74") (name "Net-(LED13-PadC)") (class "Default")
      (node (ref "LED13") (pin "C") (pinfunction "C_C") (pintype "passive"))
      (node (ref "LED14") (pin "A") (pinfunction "A_A") (pintype "passive"))
      (node (ref "R27") (pin "2") (pinfunction "2_2") (pintype "passive"))
      (node (ref "R28") (pin "2") (pinfunction "2_2") (pintype "passive"))
    )
    (net (code "75") (name "Net-(LED15-PadC)") (class "Default")
      (node (ref "LED15") (pin "C") (pinfunction "C_C") (pintype "passive"))
      (node (ref "LED16") (pin "A") (pinfunction "A_A") (pintype "passive"))
      (node (ref "R31") (pin "2") (pinfunction "2_2") (pintype "passive"))
      (node (ref "R32") (pin "2") (pinfunction "2_2") (pintype "passive"))
    )
    (net (code "76") (name "Net-(LED17-PadC)") (class "Default")
      (node (ref "LED17") (pin "C") (pinfunction "C_C") (pintype "passive"))
      (node (ref "LED18") (pin "A") (pinfunction "A_A") (pintype "passive"))
      (node (ref "R35") (pin "2") (pinfunction "2_2") (pintype "passive"))
      (node (ref "R36") (pin "2") (pinfunction "2_2") (pintype "passive"))
    )
    (net (code "77") (name "Net-(LED19-PadC)") (class "Default")
      (node (ref "LED19") (pin "C") (pinfunction "C_C") (pintype "passive"))
      (node (ref "LED20") (pin "A") (pinfunction "A_A") (pintype "passive"))
      (node (ref "R41") (pin "2") (pinfunction "2_2") (pintype "passive"))
      (node (ref "R42") (pin "2") (pinfunction "2_2") (pintype "passive"))
    )
    (net (code "78") (name "Net-(LED21-PadC)") (class "Default")
      (node (ref "LED21") (pin "C") (pinfunction "C_C") (pintype "passive"))
      (node (ref "LED22") (pin "A") (pinfunction "A_A") (pintype "passive"))
      (node (ref "R45") (pin "2") (pinfunction "2_2") (pintype "passive"))
      (node (ref "R46") (pin "2") (pinfunction "2_2") (pintype "passive"))
    )
    (net (code "79") (name "Net-(LED23-PadC)") (class "Default")
      (node (ref "LED23") (pin "C") (pinfunction "C_C") (pintype "passive"))
      (node (ref "LED24") (pin "A") (pinfunction "A_A") (pintype "passive"))
      (node (ref "R49") (pin "2") (pinfunction "2_2") (pintype "passive"))
      (node (ref "R50") (pin "2") (pinfunction "2_2") (pintype "passive"))
    )
    (net (code "80") (name "Net-(R38-S)") (class "Default")
      (node (ref "IC14") (pin "4") (pinfunction "4_4") (pintype "passive"))
      (node (ref "R38") (pin "2") (pinfunction "S_2") (pintype "passive"))
    )
    (net (code "81") (name "Net-(R39-S)") (class "Default")
      (node (ref "R39") (pin "2") (pinfunction "S_2") (pintype "passive"))
      (node (ref "SV1") (pin "3") (pinfunction "3_3") (pintype "passive"))
    )
    (net (code "82") (name "Net-(X6A-S)") (class "Default")
      (node (ref "R40") (pin "2") (pinfunction "2_2") (pintype "passive"))
      (node (ref "X6") (pin "1") (pinfunction "S_1") (pintype "passive"))
    )
    (net (code "83") (name "Net-(X6C-S)") (class "Default")
      (node (ref "IC11") (pin "4") (pinfunction "4_4") (pintype "passive"))
      (node (ref "X6") (pin "2") (pinfunction "S_2") (pintype "passive"))
    )
    (net (code "84") (name "Net-(X6D-S)") (class "Default")
      (node (ref "R44") (pin "2") (pinfunction "2_2") (pintype "passive"))
      (node (ref "X6") (pin "3") (pinfunction "S_3") (pintype "passive"))
    )
    (net (code "85") (name "Net-(X6E-S)") (class "Default")
      (node (ref "IC12") (pin "4") (pinfunction "4_4") (pintype "passive"))
      (node (ref "X6") (pin "4") (pinfunction "S_4") (pintype "passive"))
    )
    (net (code "86") (name "Net-(X6F-S)") (class "Default")
      (node (ref "R48") (pin "2") (pinfunction "2_2") (pintype "passive"))
      (node (ref "X6") (pin "5") (pinfunction "S_5") (pintype "passive"))
    )
    (net (code "87") (name "Net-(X6G-S)") (class "Default")
      (node (ref "IC13") (pin "4") (pinfunction "4_4") (pintype "passive"))
      (node (ref "X6") (pin "6") (pinfunction "S_6") (pintype "passive"))
    )
    (net (code "88") (name "Net-(X8B-S)") (class "Default")
      (node (ref "R14") (pin "2") (pinfunction "2_2") (pintype "passive"))
      (node (ref "X8") (pin "10") (pinfunction "S_10") (pintype "passive"))
    )
    (net (code "89") (name "Net-(X8D-S)") (class "Default")
      (node (ref "IC2") (pin "4") (pinfunction "4_4") (pintype "passive"))
      (node (ref "X8") (pin "3") (pinfunction "S_3") (pintype "passive"))
    )
    (net (code "90") (name "Net-(X8E-S)") (class "Default")
      (node (ref "R2") (pin "2") (pinfunction "2_2") (pintype "passive"))
      (node (ref "X8") (pin "4") (pinfunction "S_4") (pintype "passive"))
    )
    (net (code "91") (name "Net-(X8F-S)") (class "Default")
      (node (ref "IC3") (pin "4") (pinfunction "4_4") (pintype "passive"))
      (node (ref "X8") (pin "5") (pinfunction "S_5") (pintype "passive"))
    )
    (net (code "92") (name "Net-(X8G-S)") (class "Default")
      (node (ref "R7") (pin "2") (pinfunction "2_2") (pintype "passive"))
      (node (ref "X8") (pin "6") (pinfunction "S_6") (pintype "passive"))
    )
    (net (code "93") (name "Net-(X8H-S)") (class "Default")
      (node (ref "IC4") (pin "4") (pinfunction "4_4") (pintype "passive"))
      (node (ref "X8") (pin "7") (pinfunction "S_7") (pintype "passive"))
    )
    (net (code "94") (name "Net-(X8I-S)") (class "Default")
      (node (ref "R6") (pin "2") (pinfunction "2_2") (pintype "passive"))
      (node (ref "X8") (pin "8") (pinfunction "S_8") (pintype "passive"))
    )
    (net (code "95") (name "Net-(X8J-S)") (class "Default")
      (node (ref "IC5") (pin "4") (pinfunction "4_4") (pintype "passive"))
      (node (ref "X8") (pin "9") (pinfunction "S_9") (pintype "passive"))
    )
    (net (code "96") (name "Net-(X9A-S)") (class "Default")
      (node (ref "IC6") (pin "4") (pinfunction "4_4") (pintype "passive"))
      (node (ref "X9") (pin "1") (pinfunction "S_1") (pintype "passive"))
    )
    (net (code "97") (name "Net-(X9B-S)") (class "Default")
      (node (ref "R34") (pin "2") (pinfunction "2_2") (pintype "passive"))
      (node (ref "X9") (pin "10") (pinfunction "S_10") (pintype "passive"))
    )
    (net (code "98") (name "Net-(X9C-S)") (class "Default")
      (node (ref "R18") (pin "2") (pinfunction "2_2") (pintype "passive"))
      (node (ref "X9") (pin "2") (pinfunction "S_2") (pintype "passive"))
    )
    (net (code "99") (name "Net-(X9D-S)") (class "Default")
      (node (ref "IC7") (pin "4") (pinfunction "4_4") (pintype "passive"))
      (node (ref "X9") (pin "3") (pinfunction "S_3") (pintype "passive"))
    )
    (net (code "100") (name "Net-(X9E-S)") (class "Default")
      (node (ref "R22") (pin "2") (pinfunction "2_2") (pintype "passive"))
      (node (ref "X9") (pin "4") (pinfunction "S_4") (pintype "passive"))
    )
    (net (code "101") (name "Net-(X9F-S)") (class "Default")
      (node (ref "IC8") (pin "4") (pinfunction "4_4") (pintype "passive"))
      (node (ref "X9") (pin "5") (pinfunction "S_5") (pintype "passive"))
    )
    (net (code "102") (name "Net-(X9G-S)") (class "Default")
      (node (ref "R26") (pin "2") (pinfunction "2_2") (pintype "passive"))
      (node (ref "X9") (pin "6") (pinfunction "S_6") (pintype "passive"))
    )
    (net (code "103") (name "Net-(X9H-S)") (class "Default")
      (node (ref "IC9") (pin "4") (pinfunction "4_4") (pintype "passive"))
      (node (ref "X9") (pin "7") (pinfunction "S_7") (pintype "passive"))
    )
    (net (code "104") (name "Net-(X9I-S)") (class "Default")
      (node (ref "R30") (pin "2") (pinfunction "2_2") (pintype "passive"))
      (node (ref "X9") (pin "8") (pinfunction "S_8") (pintype "passive"))
    )
    (net (code "105") (name "Net-(X9J-S)") (class "Default")
      (node (ref "IC10") (pin "4") (pinfunction "4_4") (pintype "passive"))
      (node (ref "X9") (pin "9") (pinfunction "S_9") (pintype "passive"))
    )
    (net (code "106") (name "VDD") (class "Default")
      (node (ref "C2") (pin "2") (pinfunction "2_2") (pintype "passive"))
      (node (ref "C3") (pin "2") (pinfunction "2_2") (pintype "passive"))
      (node (ref "C4") (pin "2") (pinfunction "2_2") (pintype "passive"))
      (node (ref "IC1") (pin "17") (pinfunction "AVDD_17") (pintype "power_in"))
      (node (ref "IC1") (pin "28") (pinfunction "VDD_28") (pintype "power_in"))
      (node (ref "IC1") (pin "40") (pinfunction "VDD_40") (pintype "power_in"))
      (node (ref "R1") (pin "1") (pinfunction "1_1") (pintype "passive"))
      (node (ref "R38") (pin "3") (pinfunction "E_3") (pintype "passive"))
      (node (ref "R39") (pin "1") (pinfunction "A_1") (pintype "passive"))
      (node (ref "SV1") (pin "2") (pinfunction "2_2") (pintype "passive"))
      (node (ref "SV3") (pin "2") (pinfunction "2_2") (pintype "passive"))
      (node (ref "X8") (pin "1") (pinfunction "S_1") (pintype "passive"))
    )
    (net (code "107") (name "VSS") (class "Default")
      (node (ref "C1") (pin "1") (pinfunction "1_1") (pintype "passive"))
      (node (ref "C10") (pin "1") (pinfunction "1_1") (pintype "passive"))
      (node (ref "C11") (pin "1") (pinfunction "1_1") (pintype "passive"))
      (node (ref "C12") (pin "1") (pinfunction "1_1") (pintype "passive"))
      (node (ref "C13") (pin "1") (pinfunction "1_1") (pintype "passive"))
      (node (ref "C2") (pin "1") (pinfunction "1_1") (pintype "passive"))
      (node (ref "C3") (pin "1") (pinfunction "1_1") (pintype "passive"))
      (node (ref "C4") (pin "1") (pinfunction "1_1") (pintype "passive"))
      (node (ref "C5") (pin "1") (pinfunction "1_1") (pintype "passive"))
      (node (ref "C6") (pin "1") (pinfunction "1_1") (pintype "passive"))
      (node (ref "C7") (pin "1") (pinfunction "1_1") (pintype "passive"))
      (node (ref "C8") (pin "1") (pinfunction "1_1") (pintype "passive"))
      (node (ref "C9") (pin "1") (pinfunction "1_1") (pintype "passive"))
      (node (ref "D1") (pin "2") (pinfunction "A_2") (pintype "passive"))
      (node (ref "D2") (pin "2") (pinfunction "A_2") (pintype "passive"))
      (node (ref "D3") (pin "2") (pinfunction "A_2") (pintype "passive"))
      (node (ref "D4") (pin "2") (pinfunction "A_2") (pintype "passive"))
      (node (ref "D5") (pin "2") (pinfunction "A_2") (pintype "passive"))
      (node (ref "D6") (pin "2") (pinfunction "A_2") (pintype "passive"))
      (node (ref "D7") (pin "2") (pinfunction "A_2") (pintype "passive"))
      (node (ref "IC1") (pin "16") (pinfunction "AVSS_16") (pintype "power_in"))
      (node (ref "IC1") (pin "29") (pinfunction "VSS_29") (pintype "power_in"))
      (node (ref "IC1") (pin "39") (pinfunction "VSS_39") (pintype "power_in"))
      (node (ref "IC10") (pin "2") (pinfunction "2_2") (pintype "passive"))
      (node (ref "IC11") (pin "2") (pinfunction "2_2") (pintype "passive"))
      (node (ref "IC12") (pin "2") (pinfunction "2_2") (pintype "passive"))
      (node (ref "IC13") (pin "2") (pinfunction "2_2") (pintype "passive"))
      (node (ref "IC14") (pin "2") (pinfunction "2_2") (pintype "passive"))
      (node (ref "IC2") (pin "2") (pinfunction "2_2") (pintype "passive"))
      (node (ref "IC3") (pin "2") (pinfunction "2_2") (pintype "passive"))
      (node (ref "IC4") (pin "2") (pinfunction "2_2") (pintype "passive"))
      (node (ref "IC5") (pin "2") (pinfunction "2_2") (pintype "passive"))
      (node (ref "IC6") (pin "2") (pinfunction "2_2") (pintype "passive"))
      (node (ref "IC7") (pin "2") (pinfunction "2_2") (pintype "passive"))
      (node (ref "IC8") (pin "2") (pinfunction "2_2") (pintype "passive"))
      (node (ref "IC9") (pin "2") (pinfunction "2_2") (pintype "passive"))
      (node (ref "R12") (pin "1") (pinfunction "1_1") (pintype "passive"))
      (node (ref "R16") (pin "1") (pinfunction "1_1") (pintype "passive"))
      (node (ref "R20") (pin "1") (pinfunction "1_1") (pintype "passive"))
      (node (ref "R24") (pin "1") (pinfunction "1_1") (pintype "passive"))
      (node (ref "R28") (pin "1") (pinfunction "1_1") (pintype "passive"))
      (node (ref "R32") (pin "1") (pinfunction "1_1") (pintype "passive"))
      (node (ref "R36") (pin "1") (pinfunction "1_1") (pintype "passive"))
      (node (ref "R38") (pin "1") (pinfunction "A_1") (pintype "passive"))
      (node (ref "R39") (pin "3") (pinfunction "E_3") (pintype "passive"))
      (node (ref "R4") (pin "1") (pinfunction "1_1") (pintype "passive"))
      (node (ref "R42") (pin "1") (pinfunction "1_1") (pintype "passive"))
      (node (ref "R46") (pin "1") (pinfunction "1_1") (pintype "passive"))
      (node (ref "R50") (pin "1") (pinfunction "1_1") (pintype "passive"))
      (node (ref "R52") (pin "1") (pinfunction "1_1") (pintype "passive"))
      (node (ref "R53") (pin "1") (pinfunction "1_1") (pintype "passive"))
      (node (ref "R54") (pin "1") (pinfunction "1_1") (pintype "passive"))
      (node (ref "R55") (pin "1") (pinfunction "1_1") (pintype "passive"))
      (node (ref "R56") (pin "1") (pinfunction "1_1") (pintype "passive"))
      (node (ref "R57") (pin "1") (pinfunction "1_1") (pintype "passive"))
      (node (ref "R58") (pin "1") (pinfunction "1_1") (pintype "passive"))
      (node (ref "R9") (pin "1") (pinfunction "1_1") (pintype "passive"))
      (node (ref "SV1") (pin "1") (pinfunction "1_1") (pintype "passive"))
      (node (ref "SV1") (pin "10") (pinfunction "10_10") (pintype "passive"))
      (node (ref "SV1") (pin "16") (pinfunction "16_16") (pintype "passive"))
      (node (ref "SV1") (pin "5") (pinfunction "5_5") (pintype "passive"))
      (node (ref "SV1") (pin "7") (pinfunction "7_7") (pintype "passive"))
      (node (ref "SV1") (pin "8") (pinfunction "8_8") (pintype "passive"))
      (node (ref "SV1") (pin "9") (pinfunction "9_9") (pintype "passive"))
      (node (ref "SV3") (pin "3") (pinfunction "3_3") (pintype "passive"))
      (node (ref "X6") (pin "7") (pinfunction "S_7") (pintype "passive"))
      (node (ref "X6") (pin "9") (pinfunction "S_9") (pintype "passive"))
      (node (ref "X7") (pin "1") (pinfunction "S_1") (pintype "passive"))
      (node (ref "X7") (pin "3") (pinfunction "S_3") (pintype "passive"))
      (node (ref "X7") (pin "5") (pinfunction "S_5") (pintype "passive"))
      (node (ref "X7") (pin "7") (pinfunction "S_7") (pintype "passive"))
      (node (ref "X7") (pin "9") (pinfunction "S_9") (pintype "passive"))
      (node (ref "X8") (pin "2") (pinfunction "S_2") (pintype "passive"))
    )
    (net (code "108") (name "unconnected-(SV3-Pad6)") (class "Default")
      (node (ref "SV3") (pin "6") (pinfunction "6_6") (pintype "passive"))
    )
  )
)
